# canstop_2024-11-13.net
KiCad netlist of a schematic drawn in Altium Designer
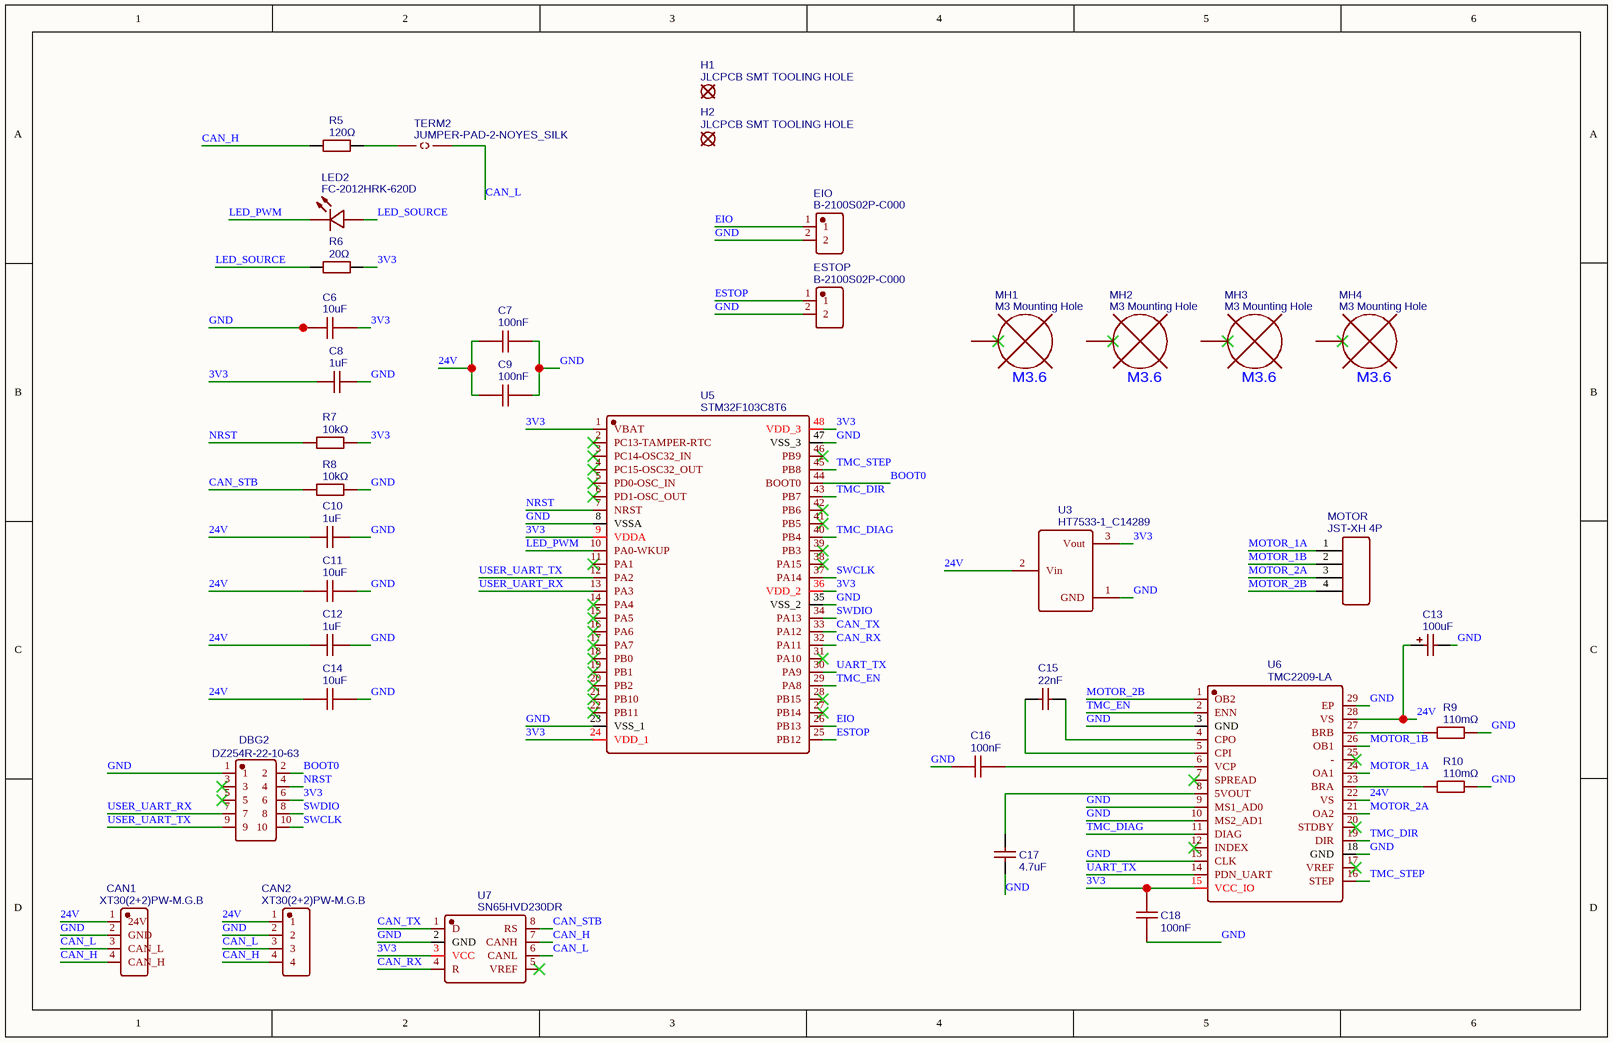
[diagram p0: canstop_2024-11-13.schdoc]

(export (version "E")
  (design (tool "Eeschema 10.0.6"))
  (components
    (comp (ref "C6")
      (value "10uF")
      (fields
        (field (name "MANUFACTURER PART") "CL21A106KAYNNNE")
        (field (name "MANUFACTURER") "SAMSUNG(三星)")
      )
      (libsource (lib "altium-import") (part "root_0_10uF_"))
    )
    (comp (ref "C7")
      (value "100nF")
      (fields
        (field (name "MANUFACTURER PART") "CC0805KRX7R9BB104")
        (field (name "MANUFACTURER") "YAGEO(国巨)")
      )
      (libsource (lib "altium-import") (part "root_0_100nF_"))
    )
    (comp (ref "C8")
      (value "1uF")
      (fields
        (field (name "MANUFACTURER PART") "CL21B105KBFNNNE")
        (field (name "MANUFACTURER") "SAMSUNG(三星)")
      )
      (libsource (lib "altium-import") (part "root_0_1uF_"))
    )
    (comp (ref "C9")
      (value "100nF")
      (fields
        (field (name "MANUFACTURER PART") "CC0805KRX7R9BB104")
        (field (name "MANUFACTURER") "YAGEO(国巨)")
      )
      (libsource (lib "altium-import") (part "root_0_100nF_"))
    )
    (comp (ref "C10")
      (value "1uF")
      (fields
        (field (name "MANUFACTURER PART") "CL21B105KBFNNNE")
        (field (name "MANUFACTURER") "SAMSUNG(三星)")
      )
      (libsource (lib "altium-import") (part "root_0_1uF_"))
    )
    (comp (ref "C11")
      (value "10uF")
      (fields
        (field (name "MANUFACTURER PART") "CL21A106KAYNNNE")
        (field (name "MANUFACTURER") "SAMSUNG(三星)")
      )
      (libsource (lib "altium-import") (part "root_0_10uF_"))
    )
    (comp (ref "C12")
      (value "1uF")
      (fields
        (field (name "MANUFACTURER PART") "CL21B105KBFNNNE")
        (field (name "MANUFACTURER") "SAMSUNG(三星)")
      )
      (libsource (lib "altium-import") (part "root_0_1uF_"))
    )
    (comp (ref "C13")
      (value "100uF")
      (fields
        (field (name "MANUFACTURER") "KEMET(基美)")
        (field (name "MANUFACTURER PART") "T491X107M025AT")
        (field (name "CONTRIBUTOR") "LCSC")
      )
      (libsource (lib "altium-import") (part "root_0_100uF_"))
    )
    (comp (ref "C14")
      (value "10uF")
      (fields
        (field (name "MANUFACTURER PART") "CL21A106KAYNNNE")
        (field (name "MANUFACTURER") "SAMSUNG(三星)")
      )
      (libsource (lib "altium-import") (part "root_0_10uF_"))
    )
    (comp (ref "C15")
      (value "22nF")
      (fields
        (field (name "MANUFACTURER PART") "CL10B223KB8NNNC")
        (field (name "MANUFACTURER") "SAMSUNG(三星)")
      )
      (libsource (lib "altium-import") (part "root_0_22nF_"))
    )
    (comp (ref "C16")
      (value "100nF")
      (fields
        (field (name "MANUFACTURER") "YAGEO(国巨)")
        (field (name "MANUFACTURER PART") "CC0603KRX7R9BB104")
      )
      (libsource (lib "altium-import") (part "root_0_100nF_"))
    )
    (comp (ref "C17")
      (value "4.7uF")
      (fields
        (field (name "MANUFACTURER PART") "CL10A475KO8NNNC")
        (field (name "MANUFACTURER") "SAMSUNG(三星)")
      )
      (libsource (lib "altium-import") (part "root_1_4.7uF_"))
    )
    (comp (ref "C18")
      (value "100nF")
      (fields
        (field (name "MANUFACTURER") "YAGEO(国巨)")
        (field (name "MANUFACTURER PART") "CC0603KRX7R9BB104")
      )
      (libsource (lib "altium-import") (part "root_1_100nF_"))
    )
    (comp (ref "CAN1")
      (value "XT30(2+2)PW-M.G.B")
      (fields (field (name "MANUFACTURER") "AMASS(艾迈斯)") (field (name "CONTRIBUTOR") "chathamja"))
      (libsource (lib "altium-import") (part "root_3_XT30(2+2)PW-M.G.B_"))
    )
    (comp (ref "CAN2")
      (value "XT30(2+2)PW-M.G.B")
      (fields (field (name "MANUFACTURER") "AMASS(艾迈斯)") (field (name "CONTRIBUTOR") "chathamja"))
      (libsource (lib "altium-import") (part "root_3_XT30(2+2)PW-M.G.B_"))
    )
    (comp (ref "DBG2")
      (value "DZ254R-22-10-63")
      (fields (field (name "MANUFACTURER") "DEALON(德艺隆)") (field (name "CONTRIBUTOR") "LCSC"))
      (libsource (lib "altium-import") (part "root_0_DZ254R-22-10-63_"))
    )
    (comp (ref "EIO")
      (value "B-2100S02P-C000")
      (fields (field (name "MANUFACTURER") "Ckmtw(灿科盟)") (field (name "CONTRIBUTOR") "LCSC"))
      (libsource (lib "altium-import") (part "root_0_B-2100S02P-C000_"))
    )
    (comp (ref "ESTOP")
      (value "B-2100S02P-C000")
      (fields (field (name "MANUFACTURER") "Ckmtw(灿科盟)") (field (name "CONTRIBUTOR") "LCSC"))
      (libsource (lib "altium-import") (part "root_0_B-2100S02P-C000_"))
    )
    (comp (ref "H1")
      (value "JLCPCB SMT TOOLING HOLE")
      (fields (field (name "CONTRIBUTOR") "Sindel90"))
      (libsource (lib "altium-import") (part "root_0_JLCPCB SMT TOOLING HOLE_"))
    )
    (comp (ref "H2")
      (value "JLCPCB SMT TOOLING HOLE")
      (fields (field (name "CONTRIBUTOR") "Sindel90"))
      (libsource (lib "altium-import") (part "root_0_JLCPCB SMT TOOLING HOLE_"))
    )
    (comp (ref "LED2")
      (value "FC-2012HRK-620D")
      (fields (field (name "MANUFACTURER") "国星光电") (field (name "MANUFACTURER PART") "NCD0805R1"))
      (libsource (lib "altium-import") (part "root_0_FC-2012HRK-620D_"))
    )
    (comp (ref "MH1")
      (value "M3 Mounting Hole")
      (fields (field (name "CONTRIBUTOR") "StefMas"))
      (libsource (lib "altium-import") (part "root_0_M3 Mounting Hole_"))
    )
    (comp (ref "MH2")
      (value "M3 Mounting Hole")
      (fields (field (name "CONTRIBUTOR") "StefMas"))
      (libsource (lib "altium-import") (part "root_0_M3 Mounting Hole_"))
    )
    (comp (ref "MH3")
      (value "M3 Mounting Hole")
      (fields (field (name "CONTRIBUTOR") "StefMas"))
      (libsource (lib "altium-import") (part "root_0_M3 Mounting Hole_"))
    )
    (comp (ref "MH4")
      (value "M3 Mounting Hole")
      (fields (field (name "CONTRIBUTOR") "StefMas"))
      (libsource (lib "altium-import") (part "root_0_M3 Mounting Hole_"))
    )
    (comp (ref "MOTOR")
      (value "JST-XH 4P")
      (fields (field (name "CONTRIBUTOR") "ordialesjeremiah"))
      (libsource (lib "altium-import") (part "root_0_JST-XH 4P_"))
    )
    (comp (ref "R5")
      (value "120Ω")
      (fields
        (field (name "MANUFACTURER") "UNI-ROYAL(厚声)")
        (field (name "MANUFACTURER PART") "0805W8F1200T5E")
      )
      (libsource (lib "altium-import") (part "root_0_120Ω_"))
    )
    (comp (ref "R6")
      (value "20Ω")
      (fields
        (field (name "MANUFACTURER") "UNI-ROYAL(厚声)")
        (field (name "MANUFACTURER PART") "0805W8F200JT5E")
      )
      (libsource (lib "altium-import") (part "root_0_20Ω_"))
    )
    (comp (ref "R7")
      (value "10kΩ")
      (fields
        (field (name "MANUFACTURER") "UNI-ROYAL(厚声)")
        (field (name "MANUFACTURER PART") "0805W8F1002T5E")
      )
      (libsource (lib "altium-import") (part "root_0_10kΩ_"))
    )
    (comp (ref "R8")
      (value "10kΩ")
      (fields
        (field (name "MANUFACTURER") "UNI-ROYAL(厚声)")
        (field (name "MANUFACTURER PART") "0805W8F1002T5E")
      )
      (libsource (lib "altium-import") (part "root_0_10kΩ_"))
    )
    (comp (ref "R9")
      (value "110mΩ")
      (fields
        (field (name "MANUFACTURER") "RALEC(旺诠)")
        (field (name "MANUFACTURER PART") "RTT12R110FTP")
        (field (name "CONTRIBUTOR") "LCSC")
      )
      (libsource (lib "altium-import") (part "root_0_110mΩ_"))
    )
    (comp (ref "R10")
      (value "110mΩ")
      (fields
        (field (name "MANUFACTURER") "RALEC(旺诠)")
        (field (name "MANUFACTURER PART") "RTT12R110FTP")
        (field (name "CONTRIBUTOR") "LCSC")
      )
      (libsource (lib "altium-import") (part "root_0_110mΩ_"))
    )
    (comp (ref "TERM2")
      (value "JUMPER-PAD-2-NOYES_SILK")
      (fields (field (name "CONTRIBUTOR") "SparkFun"))
      (libsource (lib "altium-import") (part "root_0_JUMPER-PAD-2-NOYES_SILK_"))
    )
    (comp (ref "U3")
      (value "HT7533-1_C14289")
      (fields (field (name "MANUFACTURER") "HOLTEK(合泰/盛群)") (field (name "MANUFACTURER PART") "HT7533-1"))
      (libsource (lib "altium-import") (part "root_0_HT7533-1_C14289_"))
    )
    (comp (ref "U5")
      (value "STM32F103C8T6")
      (fields (field (name "MANUFACTURER") "ST(意法半导体)"))
      (libsource (lib "altium-import") (part "root_0_STM32F103C8T6_"))
    )
    (comp (ref "U6")
      (value "TMC2209-LA")
      (fields (field (name "MANUFACTURER") "TRINAMIC") (field (name "CONTRIBUTOR") "LCSC"))
      (libsource (lib "altium-import") (part "root_0_TMC2209-LA_"))
    )
    (comp (ref "U7")
      (value "SN65HVD230DR")
      (fields (field (name "MANUFACTURER") "TI(德州仪器)"))
      (libsource (lib "altium-import") (part "root_0_SN65HVD230DR_"))
    )
  )
  (nets
    (net (code "1") (name "/3V3") (class "Default")
      (node (ref "C18") (pin "2") (pinfunction "2_2") (pintype "passive"))
      (node (ref "C6") (pin "2") (pinfunction "2_2") (pintype "passive"))
      (node (ref "C8") (pin "1") (pinfunction "1_1") (pintype "passive"))
      (node (ref "DBG2") (pin "6") (pinfunction "6_6") (pintype "passive"))
      (node (ref "R6") (pin "2") (pinfunction "2_2") (pintype "passive"))
      (node (ref "R7") (pin "2") (pinfunction "2_2") (pintype "passive"))
      (node (ref "U3") (pin "3") (pinfunction "Vout_3") (pintype "passive"))
      (node (ref "U5") (pin "1") (pinfunction "VBAT_1") (pintype "passive"))
      (node (ref "U5") (pin "24") (pinfunction "VDD_1_24") (pintype "passive"))
      (node (ref "U5") (pin "36") (pinfunction "VDD_2_36") (pintype "passive"))
      (node (ref "U5") (pin "48") (pinfunction "VDD_3_48") (pintype "passive"))
      (node (ref "U5") (pin "9") (pinfunction "VDDA_9") (pintype "passive"))
      (node (ref "U6") (pin "15") (pinfunction "VCC_IO_15") (pintype "passive"))
      (node (ref "U7") (pin "3") (pinfunction "VCC_3") (pintype "passive"))
    )
    (net (code "2") (name "/24V") (class "Default")
      (node (ref "C10") (pin "1") (pinfunction "1_1") (pintype "passive"))
      (node (ref "C11") (pin "1") (pinfunction "1_1") (pintype "passive"))
      (node (ref "C12") (pin "1") (pinfunction "1_1") (pintype "passive"))
      (node (ref "C13") (pin "1") (pinfunction "1_1") (pintype "passive"))
      (node (ref "C14") (pin "1") (pinfunction "1_1") (pintype "passive"))
      (node (ref "C7") (pin "1") (pinfunction "1_1") (pintype "passive"))
      (node (ref "C9") (pin "1") (pinfunction "1_1") (pintype "passive"))
      (node (ref "CAN1") (pin "1") (pinfunction "24V_1") (pintype "passive"))
      (node (ref "CAN2") (pin "1") (pinfunction "24V_1") (pintype "passive"))
      (node (ref "U3") (pin "2") (pinfunction "Vin_2") (pintype "passive"))
      (node (ref "U6") (pin "22") (pinfunction "VS_22") (pintype "passive"))
      (node (ref "U6") (pin "28") (pinfunction "VS_28") (pintype "passive"))
    )
    (net (code "3") (name "/BOOT0") (class "Default")
      (node (ref "DBG2") (pin "2") (pinfunction "2_2") (pintype "passive"))
      (node (ref "U5") (pin "44") (pinfunction "BOOT0_44") (pintype "passive"))
    )
    (net (code "4") (name "/CAN_H") (class "Default")
      (node (ref "CAN1") (pin "4") (pinfunction "CAN_H_4") (pintype "passive"))
      (node (ref "CAN2") (pin "4") (pinfunction "CAN_H_4") (pintype "passive"))
      (node (ref "R5") (pin "1") (pinfunction "1_1") (pintype "passive"))
      (node (ref "U7") (pin "7") (pinfunction "CANH_7") (pintype "passive"))
    )
    (net (code "5") (name "/CAN_L") (class "Default")
      (node (ref "CAN1") (pin "3") (pinfunction "CAN_L_3") (pintype "passive"))
      (node (ref "CAN2") (pin "3") (pinfunction "CAN_L_3") (pintype "passive"))
      (node (ref "TERM2") (pin "2") (pinfunction "2_2") (pintype "passive"))
      (node (ref "U7") (pin "6") (pinfunction "CANL_6") (pintype "passive"))
    )
    (net (code "6") (name "/CAN_RX") (class "Default")
      (node (ref "U5") (pin "32") (pinfunction "PA11_32") (pintype "passive"))
      (node (ref "U7") (pin "4") (pinfunction "R_4") (pintype "passive"))
    )
    (net (code "7") (name "/CAN_STB") (class "Default")
      (node (ref "R8") (pin "1") (pinfunction "1_1") (pintype "passive"))
      (node (ref "U7") (pin "8") (pinfunction "RS_8") (pintype "passive"))
    )
    (net (code "8") (name "/CAN_TX") (class "Default")
      (node (ref "U5") (pin "33") (pinfunction "PA12_33") (pintype "passive"))
      (node (ref "U7") (pin "1") (pinfunction "D_1") (pintype "passive"))
    )
    (net (code "9") (name "/EIO") (class "Default")
      (node (ref "EIO") (pin "1") (pinfunction "1_1") (pintype "passive"))
      (node (ref "U5") (pin "26") (pinfunction "PB13_26") (pintype "passive"))
    )
    (net (code "10") (name "/ESTOP") (class "Default")
      (node (ref "ESTOP") (pin "1") (pinfunction "1_1") (pintype "passive"))
      (node (ref "U5") (pin "25") (pinfunction "PB12_25") (pintype "passive"))
    )
    (net (code "11") (name "/GND") (class "Default")
      (node (ref "C10") (pin "2") (pinfunction "2_2") (pintype "passive"))
      (node (ref "C11") (pin "2") (pinfunction "2_2") (pintype "passive"))
      (node (ref "C12") (pin "2") (pinfunction "2_2") (pintype "passive"))
      (node (ref "C13") (pin "2") (pinfunction "2_2") (pintype "passive"))
      (node (ref "C14") (pin "2") (pinfunction "2_2") (pintype "passive"))
      (node (ref "C16") (pin "1") (pinfunction "1_1") (pintype "passive"))
      (node (ref "C17") (pin "1") (pinfunction "1_1") (pintype "passive"))
      (node (ref "C18") (pin "1") (pinfunction "1_1") (pintype "passive"))
      (node (ref "C6") (pin "1") (pinfunction "1_1") (pintype "passive"))
      (node (ref "C7") (pin "2") (pinfunction "2_2") (pintype "passive"))
      (node (ref "C8") (pin "2") (pinfunction "2_2") (pintype "passive"))
      (node (ref "C9") (pin "2") (pinfunction "2_2") (pintype "passive"))
      (node (ref "CAN1") (pin "2") (pinfunction "GND_2") (pintype "passive"))
      (node (ref "CAN2") (pin "2") (pinfunction "GND_2") (pintype "passive"))
      (node (ref "DBG2") (pin "1") (pinfunction "1_1") (pintype "passive"))
      (node (ref "EIO") (pin "2") (pinfunction "2_2") (pintype "passive"))
      (node (ref "ESTOP") (pin "2") (pinfunction "2_2") (pintype "passive"))
      (node (ref "R10") (pin "2") (pinfunction "2_2") (pintype "passive"))
      (node (ref "R8") (pin "2") (pinfunction "2_2") (pintype "passive"))
      (node (ref "R9") (pin "2") (pinfunction "2_2") (pintype "passive"))
      (node (ref "U3") (pin "1") (pinfunction "GND_1") (pintype "passive"))
      (node (ref "U5") (pin "23") (pinfunction "VSS_1_23") (pintype "passive"))
      (node (ref "U5") (pin "35") (pinfunction "VSS_2_35") (pintype "passive"))
      (node (ref "U5") (pin "47") (pinfunction "VSS_3_47") (pintype "passive"))
      (node (ref "U5") (pin "8") (pinfunction "VSSA_8") (pintype "passive"))
      (node (ref "U6") (pin "10") (pinfunction "MS2_AD1_10") (pintype "passive"))
      (node (ref "U6") (pin "13") (pinfunction "CLK_13") (pintype "passive"))
      (node (ref "U6") (pin "18") (pinfunction "GND_18") (pintype "passive"))
      (node (ref "U6") (pin "29") (pinfunction "EP_29") (pintype "passive"))
      (node (ref "U6") (pin "3") (pinfunction "GND_3") (pintype "passive"))
      (node (ref "U6") (pin "9") (pinfunction "MS1_AD0_9") (pintype "passive"))
      (node (ref "U7") (pin "2") (pinfunction "GND_2") (pintype "passive"))
    )
    (net (code "12") (name "/LED_PWM") (class "Default")
      (node (ref "LED2") (pin "2") (pinfunction "-_2") (pintype "passive"))
      (node (ref "U5") (pin "10") (pinfunction "PA0-WKUP_10") (pintype "passive"))
    )
    (net (code "13") (name "/LED_SOURCE") (class "Default")
      (node (ref "LED2") (pin "1") (pinfunction "+_1") (pintype "passive"))
      (node (ref "R6") (pin "1") (pinfunction "1_1") (pintype "passive"))
    )
    (net (code "14") (name "/MOTOR_1A") (class "Default")
      (node (ref "MOTOR") (pin "1") (pinfunction "1_1") (pintype "passive"))
      (node (ref "U6") (pin "24") (pinfunction "OA1_24") (pintype "passive"))
    )
    (net (code "15") (name "/MOTOR_1B") (class "Default")
      (node (ref "MOTOR") (pin "2") (pinfunction "2_2") (pintype "passive"))
      (node (ref "U6") (pin "26") (pinfunction "OB1_26") (pintype "passive"))
    )
    (net (code "16") (name "/MOTOR_2A") (class "Default")
      (node (ref "MOTOR") (pin "3") (pinfunction "3_3") (pintype "passive"))
      (node (ref "U6") (pin "21") (pinfunction "OA2_21") (pintype "passive"))
    )
    (net (code "17") (name "/MOTOR_2B") (class "Default")
      (node (ref "MOTOR") (pin "4") (pinfunction "4_4") (pintype "passive"))
      (node (ref "U6") (pin "1") (pinfunction "OB2_1") (pintype "passive"))
    )
    (net (code "18") (name "/NRST") (class "Default")
      (node (ref "DBG2") (pin "4") (pinfunction "4_4") (pintype "passive"))
      (node (ref "R7") (pin "1") (pinfunction "1_1") (pintype "passive"))
      (node (ref "U5") (pin "7") (pinfunction "NRST_7") (pintype "passive"))
    )
    (net (code "19") (name "/SWCLK") (class "Default")
      (node (ref "DBG2") (pin "10") (pinfunction "10_10") (pintype "passive"))
      (node (ref "U5") (pin "37") (pinfunction "PA14_37") (pintype "passive"))
    )
    (net (code "20") (name "/SWDIO") (class "Default")
      (node (ref "DBG2") (pin "8") (pinfunction "8_8") (pintype "passive"))
      (node (ref "U5") (pin "34") (pinfunction "PA13_34") (pintype "passive"))
    )
    (net (code "21") (name "/TMC_DIAG") (class "Default")
      (node (ref "U5") (pin "40") (pinfunction "PB4_40") (pintype "passive"))
      (node (ref "U6") (pin "11") (pinfunction "DIAG_11") (pintype "passive"))
    )
    (net (code "22") (name "/TMC_DIR") (class "Default")
      (node (ref "U5") (pin "43") (pinfunction "PB7_43") (pintype "passive"))
      (node (ref "U6") (pin "19") (pinfunction "DIR_19") (pintype "passive"))
    )
    (net (code "23") (name "/TMC_EN") (class "Default")
      (node (ref "U5") (pin "29") (pinfunction "PA8_29") (pintype "passive"))
      (node (ref "U6") (pin "2") (pinfunction "ENN_2") (pintype "passive"))
    )
    (net (code "24") (name "/TMC_STEP") (class "Default")
      (node (ref "U5") (pin "45") (pinfunction "PB8_45") (pintype "passive"))
      (node (ref "U6") (pin "16") (pinfunction "STEP_16") (pintype "passive"))
    )
    (net (code "25") (name "/UART_TX") (class "Default")
      (node (ref "U5") (pin "30") (pinfunction "PA9_30") (pintype "passive"))
      (node (ref "U6") (pin "14") (pinfunction "PDN_UART_14") (pintype "passive"))
    )
    (net (code "26") (name "/USER_UART_RX") (class "Default")
      (node (ref "DBG2") (pin "7") (pinfunction "7_7") (pintype "passive"))
      (node (ref "U5") (pin "13") (pinfunction "PA3_13") (pintype "passive"))
    )
    (net (code "27") (name "/USER_UART_TX") (class "Default")
      (node (ref "DBG2") (pin "9") (pinfunction "9_9") (pintype "passive"))
      (node (ref "U5") (pin "12") (pinfunction "PA2_12") (pintype "passive"))
    )
    (net (code "28") (name "Net-(R5-Pad2)") (class "Default")
      (node (ref "R5") (pin "2") (pinfunction "2_2") (pintype "passive"))
      (node (ref "TERM2") (pin "1") (pinfunction "1_1") (pintype "passive"))
    )
    (net (code "29") (name "Net-(U6-5VOUT)") (class "Default")
      (node (ref "C17") (pin "2") (pinfunction "2_2") (pintype "passive"))
      (node (ref "U6") (pin "8") (pinfunction "5VOUT_8") (pintype "passive"))
    )
    (net (code "30") (name "Net-(U6-BRA)") (class "Default")
      (node (ref "R10") (pin "1") (pinfunction "1_1") (pintype "passive"))
      (node (ref "U6") (pin "23") (pinfunction "BRA_23") (pintype "passive"))
    )
    (net (code "31") (name "Net-(U6-BRB)") (class "Default")
      (node (ref "R9") (pin "1") (pinfunction "1_1") (pintype "passive"))
      (node (ref "U6") (pin "27") (pinfunction "BRB_27") (pintype "passive"))
    )
    (net (code "32") (name "Net-(U6-CPI)") (class "Default")
      (node (ref "C15") (pin "1") (pinfunction "1_1") (pintype "passive"))
      (node (ref "U6") (pin "5") (pinfunction "CPI_5") (pintype "passive"))
    )
    (net (code "33") (name "Net-(U6-CPO)") (class "Default")
      (node (ref "C15") (pin "2") (pinfunction "2_2") (pintype "passive"))
      (node (ref "U6") (pin "4") (pinfunction "CPO_4") (pintype "passive"))
    )
    (net (code "34") (name "Net-(U6-VCP)") (class "Default")
      (node (ref "C16") (pin "2") (pinfunction "2_2") (pintype "passive"))
      (node (ref "U6") (pin "6") (pinfunction "VCP_6") (pintype "passive"))
    )
    (net (code "35") (name "unconnected-(DBG2-Pad3)") (class "Default")
      (node (ref "DBG2") (pin "3") (pinfunction "3_3") (pintype "passive+no_connect"))
    )
    (net (code "36") (name "unconnected-(DBG2-Pad5)") (class "Default")
      (node (ref "DBG2") (pin "5") (pinfunction "5_5") (pintype "passive+no_connect"))
    )
    (net (code "37") (name "unconnected-(MH1-Pad1)") (class "Default")
      (node (ref "MH1") (pin "1") (pinfunction "1_1") (pintype "passive+no_connect"))
    )
    (net (code "38") (name "unconnected-(MH2-Pad1)") (class "Default")
      (node (ref "MH2") (pin "1") (pinfunction "1_1") (pintype "passive+no_connect"))
    )
    (net (code "39") (name "unconnected-(MH3-Pad1)") (class "Default")
      (node (ref "MH3") (pin "1") (pinfunction "1_1") (pintype "passive+no_connect"))
    )
    (net (code "40") (name "unconnected-(MH4-Pad1)") (class "Default")
      (node (ref "MH4") (pin "1") (pinfunction "1_1") (pintype "passive+no_connect"))
    )
    (net (code "41") (name "unconnected-(U5-PA1-Pad11)") (class "Default")
      (node (ref "U5") (pin "11") (pinfunction "PA1_11") (pintype "passive+no_connect"))
    )
    (net (code "42") (name "unconnected-(U5-PA4-Pad14)") (class "Default")
      (node (ref "U5") (pin "14") (pinfunction "PA4_14") (pintype "passive+no_connect"))
    )
    (net (code "43") (name "unconnected-(U5-PA5-Pad15)") (class "Default")
      (node (ref "U5") (pin "15") (pinfunction "PA5_15") (pintype "passive+no_connect"))
    )
    (net (code "44") (name "unconnected-(U5-PA6-Pad16)") (class "Default")
      (node (ref "U5") (pin "16") (pinfunction "PA6_16") (pintype "passive+no_connect"))
    )
    (net (code "45") (name "unconnected-(U5-PA7-Pad17)") (class "Default")
      (node (ref "U5") (pin "17") (pinfunction "PA7_17") (pintype "passive+no_connect"))
    )
    (net (code "46") (name "unconnected-(U5-PA10-Pad31)") (class "Default")
      (node (ref "U5") (pin "31") (pinfunction "PA10_31") (pintype "passive+no_connect"))
    )
    (net (code "47") (name "unconnected-(U5-PA15-Pad38)") (class "Default")
      (node (ref "U5") (pin "38") (pinfunction "PA15_38") (pintype "passive+no_connect"))
    )
    (net (code "48") (name "unconnected-(U5-PB0-Pad18)") (class "Default")
      (node (ref "U5") (pin "18") (pinfunction "PB0_18") (pintype "passive+no_connect"))
    )
    (net (code "49") (name "unconnected-(U5-PB1-Pad19)") (class "Default")
      (node (ref "U5") (pin "19") (pinfunction "PB1_19") (pintype "passive+no_connect"))
    )
    (net (code "50") (name "unconnected-(U5-PB2-Pad20)") (class "Default")
      (node (ref "U5") (pin "20") (pinfunction "PB2_20") (pintype "passive+no_connect"))
    )
    (net (code "51") (name "unconnected-(U5-PB3-Pad39)") (class "Default")
      (node (ref "U5") (pin "39") (pinfunction "PB3_39") (pintype "passive+no_connect"))
    )
    (net (code "52") (name "unconnected-(U5-PB5-Pad41)") (class "Default")
      (node (ref "U5") (pin "41") (pinfunction "PB5_41") (pintype "passive+no_connect"))
    )
    (net (code "53") (name "unconnected-(U5-PB6-Pad42)") (class "Default")
      (node (ref "U5") (pin "42") (pinfunction "PB6_42") (pintype "passive+no_connect"))
    )
    (net (code "54") (name "unconnected-(U5-PB9-Pad46)") (class "Default")
      (node (ref "U5") (pin "46") (pinfunction "PB9_46") (pintype "passive+no_connect"))
    )
    (net (code "55") (name "unconnected-(U5-PB10-Pad21)") (class "Default")
      (node (ref "U5") (pin "21") (pinfunction "PB10_21") (pintype "passive+no_connect"))
    )
    (net (code "56") (name "unconnected-(U5-PB11-Pad22)") (class "Default")
      (node (ref "U5") (pin "22") (pinfunction "PB11_22") (pintype "passive+no_connect"))
    )
    (net (code "57") (name "unconnected-(U5-PB14-Pad27)") (class "Default")
      (node (ref "U5") (pin "27") (pinfunction "PB14_27") (pintype "passive+no_connect"))
    )
    (net (code "58") (name "unconnected-(U5-PB15-Pad28)") (class "Default")
      (node (ref "U5") (pin "28") (pinfunction "PB15_28") (pintype "passive+no_connect"))
    )
    (net (code "59") (name "unconnected-(U5-PC13-TAMPER-RTC-Pad2)") (class "Default")
      (node (ref "U5") (pin "2") (pinfunction "PC13-TAMPER-RTC_2") (pintype "passive+no_connect"))
    )
    (net (code "60") (name "unconnected-(U5-PC14-OSC32_IN-Pad3)") (class "Default")
      (node (ref "U5") (pin "3") (pinfunction "PC14-OSC32_IN_3") (pintype "passive+no_connect"))
    )
    (net (code "61") (name "unconnected-(U5-PC15-OSC32_OUT-Pad4)") (class "Default")
      (node (ref "U5") (pin "4") (pinfunction "PC15-OSC32_OUT_4") (pintype "passive+no_connect"))
    )
    (net (code "62") (name "unconnected-(U5-PD0-OSC_IN-Pad5)") (class "Default")
      (node (ref "U5") (pin "5") (pinfunction "PD0-OSC_IN_5") (pintype "passive+no_connect"))
    )
    (net (code "63") (name "unconnected-(U5-PD1-OSC_OUT-Pad6)") (class "Default")
      (node (ref "U5") (pin "6") (pinfunction "PD1-OSC_OUT_6") (pintype "passive+no_connect"))
    )
    (net (code "64") (name "unconnected-(U6---Pad25)") (class "Default")
      (node (ref "U6") (pin "25") (pinfunction "-_25") (pintype "passive+no_connect"))
    )
    (net (code "65") (name "unconnected-(U6-INDEX-Pad12)") (class "Default")
      (node (ref "U6") (pin "12") (pinfunction "INDEX_12") (pintype "passive+no_connect"))
    )
    (net (code "66") (name "unconnected-(U6-SPREAD-Pad7)") (class "Default")
      (node (ref "U6") (pin "7") (pinfunction "SPREAD_7") (pintype "passive+no_connect"))
    )
    (net (code "67") (name "unconnected-(U6-STDBY-Pad20)") (class "Default")
      (node (ref "U6") (pin "20") (pinfunction "STDBY_20") (pintype "passive+no_connect"))
    )
    (net (code "68") (name "unconnected-(U6-VREF-Pad17)") (class "Default")
      (node (ref "U6") (pin "17") (pinfunction "VREF_17") (pintype "passive+no_connect"))
    )
    (net (code "69") (name "unconnected-(U7-VREF-Pad5)") (class "Default")
      (node (ref "U7") (pin "5") (pinfunction "VREF_5") (pintype "passive+no_connect"))
    )
  )
)
